# mc_psu_v2.net
KiCad netlist of a schematic drawn in EAGLE
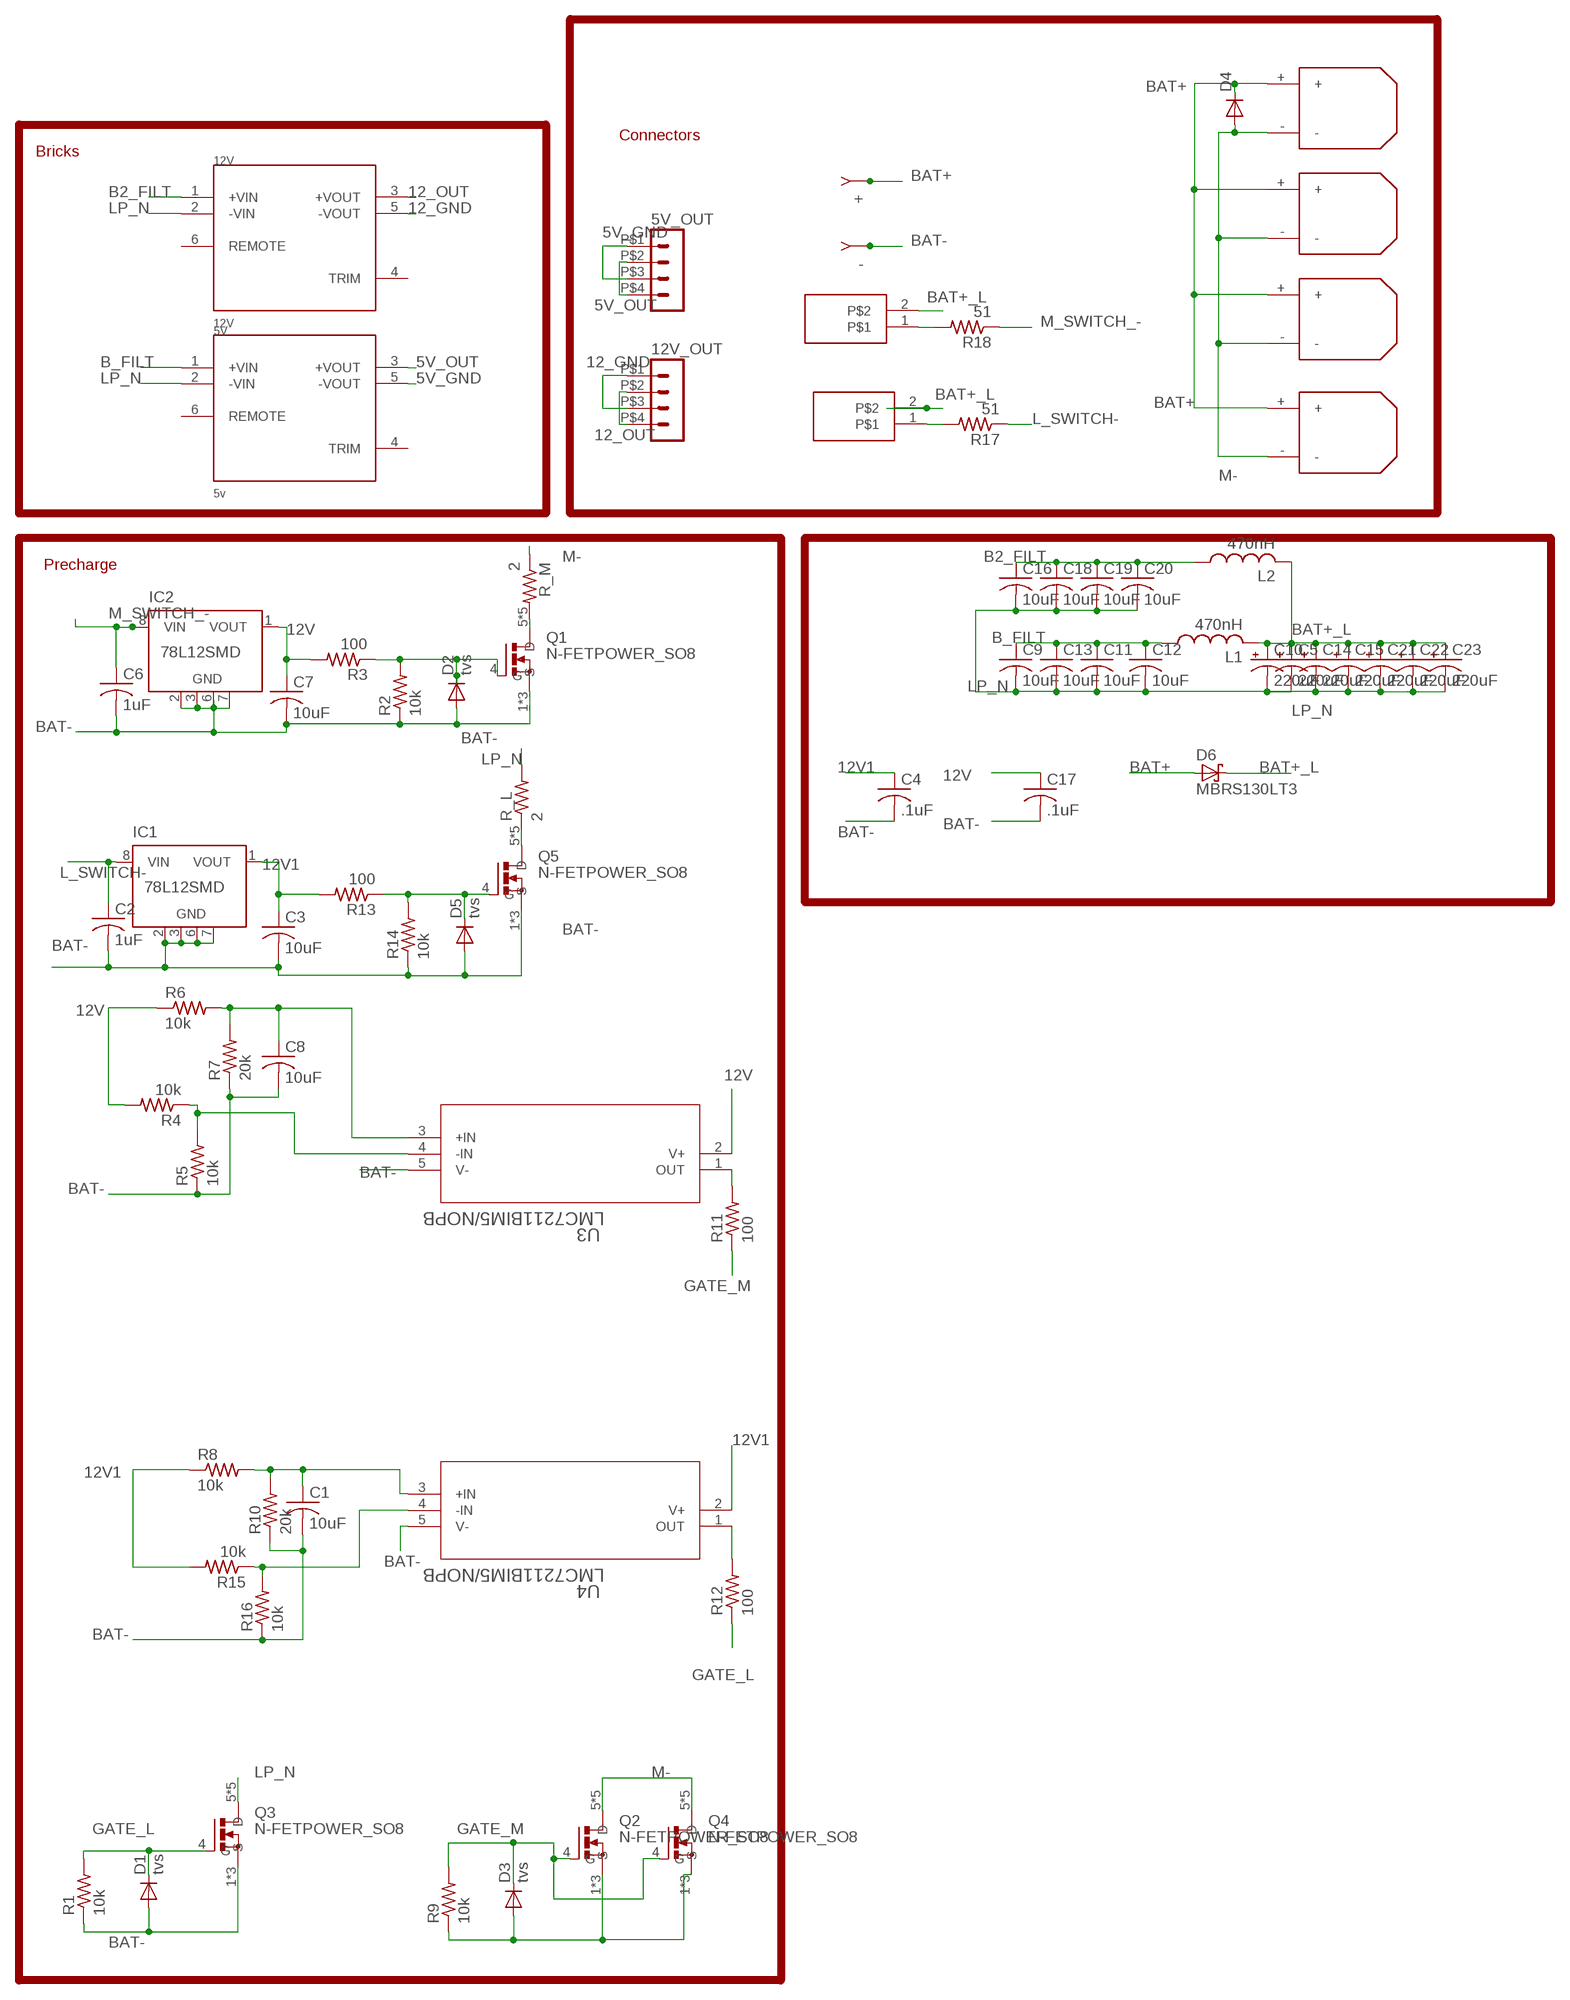
[diagram p0: schematic, sheet 1]

(export (version "E")
  (design (tool "Eeschema 10.0.6"))
  (components
    (comp (ref "+")
      (value "QFIT")
      (footprint "eagle-import:FASTON")
      (libsource (lib "eagle-import") (part "QFIT"))
    )
    (comp (ref "-")
      (value "QFIT")
      (footprint "eagle-import:FASTON")
      (libsource (lib "eagle-import") (part "QFIT"))
    )
    (comp (ref "5V")
      (value "5v")
      (footprint "eagle-import:CONV_PDQ30-Q24-S5-D")
      (fields
        (field (name "DIGI-KEY_PART_NUMBER") "102-3891-ND")
        (field (name "MF") "CUI")
        (field (name "MP") "PDQ30-Q24-S5-D")
      )
      (libsource (lib "eagle-import") (part "PDQ30-Q24-S5-D"))
    )
    (comp (ref "5V_OUT")
      (value "HEADER_POS4_43045-0401")
      (footprint "eagle-import:43045-0400")
      (libsource (lib "eagle-import") (part "HEADER_POS4_?43045-0401"))
    )
    (comp (ref "12V")
      (value "12V")
      (footprint "eagle-import:CONV_PDQ30-Q24-S5-D")
      (fields
        (field (name "DIGI-KEY_PART_NUMBER") "102-3891-ND")
        (field (name "MF") "CUI")
        (field (name "MP") "PDQ30-Q24-S5-D")
      )
      (libsource (lib "eagle-import") (part "PDQ30-Q24-S5-D"))
    )
    (comp (ref "12V_OUT")
      (value "HEADER_POS4_43045-0401")
      (footprint "eagle-import:43045-0400")
      (libsource (lib "eagle-import") (part "HEADER_POS4_?43045-0401"))
    )
    (comp (ref "C1")
      (value "10uF")
      (footprint "eagle-import:C0603K")
      (libsource (lib "eagle-import") (part "C-USC0603K"))
    )
    (comp (ref "C2")
      (value "1uF")
      (footprint "eagle-import:C0603K")
      (libsource (lib "eagle-import") (part "C-USC0603K"))
    )
    (comp (ref "C3")
      (value "10uF")
      (footprint "eagle-import:C0603K")
      (libsource (lib "eagle-import") (part "C-USC0603K"))
    )
    (comp (ref "C4")
      (value ".1uF")
      (footprint "eagle-import:C0603K")
      (libsource (lib "eagle-import") (part "C-USC0603K"))
    )
    (comp (ref "C5")
      (value "220uF")
      (footprint "eagle-import:E3,5-8")
      (libsource (lib "eagle-import") (part "CPOL-USE3.5-8"))
    )
    (comp (ref "C6")
      (value "1uF")
      (footprint "eagle-import:C0603K")
      (libsource (lib "eagle-import") (part "C-USC0603K"))
    )
    (comp (ref "C7")
      (value "10uF")
      (footprint "eagle-import:C0603K")
      (libsource (lib "eagle-import") (part "C-USC0603K"))
    )
    (comp (ref "C8")
      (value "10uF")
      (footprint "eagle-import:C0603K")
      (libsource (lib "eagle-import") (part "C-USC0603K"))
    )
    (comp (ref "C9")
      (value "10uF")
      (footprint "eagle-import:C1206K")
      (libsource (lib "eagle-import") (part "C-USC1206K"))
    )
    (comp (ref "C10")
      (value "220uF")
      (footprint "eagle-import:E3,5-8")
      (libsource (lib "eagle-import") (part "CPOL-USE3.5-8"))
    )
    (comp (ref "C11")
      (value "10uF")
      (footprint "eagle-import:C1206K")
      (libsource (lib "eagle-import") (part "C-USC1206K"))
    )
    (comp (ref "C12")
      (value "10uF")
      (footprint "eagle-import:C1206K")
      (libsource (lib "eagle-import") (part "C-USC1206K"))
    )
    (comp (ref "C13")
      (value "10uF")
      (footprint "eagle-import:C1206K")
      (libsource (lib "eagle-import") (part "C-USC1206K"))
    )
    (comp (ref "C14")
      (value "220uF")
      (footprint "eagle-import:E3,5-8")
      (libsource (lib "eagle-import") (part "CPOL-USE3.5-8"))
    )
    (comp (ref "C15")
      (value "220uF")
      (footprint "eagle-import:E3,5-8")
      (libsource (lib "eagle-import") (part "CPOL-USE3.5-8"))
    )
    (comp (ref "C16")
      (value "10uF")
      (footprint "eagle-import:C1206K")
      (libsource (lib "eagle-import") (part "C-USC1206K"))
    )
    (comp (ref "C17")
      (value ".1uF")
      (footprint "eagle-import:C0603K")
      (libsource (lib "eagle-import") (part "C-USC0603K"))
    )
    (comp (ref "C18")
      (value "10uF")
      (footprint "eagle-import:C1206K")
      (libsource (lib "eagle-import") (part "C-USC1206K"))
    )
    (comp (ref "C19")
      (value "10uF")
      (footprint "eagle-import:C1206K")
      (libsource (lib "eagle-import") (part "C-USC1206K"))
    )
    (comp (ref "C20")
      (value "10uF")
      (footprint "eagle-import:C1206K")
      (libsource (lib "eagle-import") (part "C-USC1206K"))
    )
    (comp (ref "C21")
      (value "220uF")
      (footprint "eagle-import:E3,5-8")
      (libsource (lib "eagle-import") (part "CPOL-USE3.5-8"))
    )
    (comp (ref "C22")
      (value "220uF")
      (footprint "eagle-import:E3,5-8")
      (libsource (lib "eagle-import") (part "CPOL-USE3.5-8"))
    )
    (comp (ref "C23")
      (value "220uF")
      (footprint "eagle-import:E3,5-8")
      (libsource (lib "eagle-import") (part "CPOL-USE3.5-8"))
    )
    (comp (ref "D1")
      (value "tvs")
      (footprint "eagle-import:DO214AC")
      (libsource (lib "eagle-import") (part "DIODE-DO214AC"))
    )
    (comp (ref "D2")
      (value "tvs")
      (footprint "eagle-import:DO214AC")
      (libsource (lib "eagle-import") (part "DIODE-DO214AC"))
    )
    (comp (ref "D3")
      (value "tvs")
      (footprint "eagle-import:DO214AC")
      (libsource (lib "eagle-import") (part "DIODE-DO214AC"))
    )
    (comp (ref "D4")
      (value "DIODE-SMB")
      (footprint "eagle-import:SMB")
      (libsource (lib "eagle-import") (part "DIODE-SMB"))
    )
    (comp (ref "D5")
      (value "tvs")
      (footprint "eagle-import:DO214AC")
      (libsource (lib "eagle-import") (part "DIODE-DO214AC"))
    )
    (comp (ref "D6")
      (value "MBRS130LT3")
      (footprint "eagle-import:SMB")
      (libsource (lib "eagle-import") (part "MBRS130LT3"))
    )
    (comp (ref "IC1")
      (value "78L12SMD")
      (footprint "eagle-import:SO08")
      (libsource (lib "eagle-import") (part "78LSMD12"))
    )
    (comp (ref "IC2")
      (value "78L12SMD")
      (footprint "eagle-import:SO08")
      (libsource (lib "eagle-import") (part "78LSMD12"))
    )
    (comp (ref "L1")
      (value "470nH")
      (footprint "eagle-import:L3225P")
      (libsource (lib "eagle-import") (part "L-USL3225P"))
    )
    (comp (ref "L2")
      (value "470nH")
      (footprint "eagle-import:L3225P")
      (libsource (lib "eagle-import") (part "L-USL3225P"))
    )
    (comp (ref "Q1")
      (value "N-FETPOWER_SO8")
      (footprint "eagle-import:TRANS_TPH5900CNH,L1Q")
      (libsource (lib "eagle-import") (part "N-FETPOWER_SO8"))
    )
    (comp (ref "Q2")
      (value "N-FETPOWER_SO8")
      (footprint "eagle-import:TRANS_TPH5900CNH,L1Q")
      (libsource (lib "eagle-import") (part "N-FETPOWER_SO8"))
    )
    (comp (ref "Q3")
      (value "N-FETPOWER_SO8")
      (footprint "eagle-import:TRANS_TPH5900CNH,L1Q")
      (libsource (lib "eagle-import") (part "N-FETPOWER_SO8"))
    )
    (comp (ref "Q4")
      (value "N-FETPOWER_SO8")
      (footprint "eagle-import:TRANS_TPH5900CNH,L1Q")
      (libsource (lib "eagle-import") (part "N-FETPOWER_SO8"))
    )
    (comp (ref "Q5")
      (value "N-FETPOWER_SO8")
      (footprint "eagle-import:TRANS_TPH5900CNH,L1Q")
      (libsource (lib "eagle-import") (part "N-FETPOWER_SO8"))
    )
    (comp (ref "R1")
      (value "10k")
      (footprint "eagle-import:R0402")
      (libsource (lib "eagle-import") (part "R-US_R0402"))
    )
    (comp (ref "R2")
      (value "10k")
      (footprint "eagle-import:R0402")
      (libsource (lib "eagle-import") (part "R-US_R0402"))
    )
    (comp (ref "R3")
      (value "100")
      (footprint "eagle-import:R0402")
      (libsource (lib "eagle-import") (part "R-US_R0402"))
    )
    (comp (ref "R4")
      (value "10k")
      (footprint "eagle-import:R0402")
      (libsource (lib "eagle-import") (part "R-US_R0402"))
    )
    (comp (ref "R5")
      (value "10k")
      (footprint "eagle-import:R0402")
      (libsource (lib "eagle-import") (part "R-US_R0402"))
    )
    (comp (ref "R6")
      (value "10k")
      (footprint "eagle-import:R0402")
      (libsource (lib "eagle-import") (part "R-US_R0402"))
    )
    (comp (ref "R7")
      (value "20k")
      (footprint "eagle-import:R0402")
      (libsource (lib "eagle-import") (part "R-US_R0402"))
    )
    (comp (ref "R8")
      (value "10k")
      (footprint "eagle-import:R0402")
      (libsource (lib "eagle-import") (part "R-US_R0402"))
    )
    (comp (ref "R9")
      (value "10k")
      (footprint "eagle-import:R0402")
      (libsource (lib "eagle-import") (part "R-US_R0402"))
    )
    (comp (ref "R10")
      (value "20k")
      (footprint "eagle-import:R0402")
      (libsource (lib "eagle-import") (part "R-US_R0402"))
    )
    (comp (ref "R11")
      (value "100")
      (footprint "eagle-import:R0402")
      (libsource (lib "eagle-import") (part "R-US_R0402"))
    )
    (comp (ref "R12")
      (value "100")
      (footprint "eagle-import:R0402")
      (libsource (lib "eagle-import") (part "R-US_R0402"))
    )
    (comp (ref "R13")
      (value "100")
      (footprint "eagle-import:R0402")
      (libsource (lib "eagle-import") (part "R-US_R0402"))
    )
    (comp (ref "R14")
      (value "10k")
      (footprint "eagle-import:R0402")
      (libsource (lib "eagle-import") (part "R-US_R0402"))
    )
    (comp (ref "R15")
      (value "10k")
      (footprint "eagle-import:R0402")
      (libsource (lib "eagle-import") (part "R-US_R0402"))
    )
    (comp (ref "R16")
      (value "10k")
      (footprint "eagle-import:R0402")
      (libsource (lib "eagle-import") (part "R-US_R0402"))
    )
    (comp (ref "R17")
      (value "51")
      (footprint "eagle-import:R0603")
      (libsource (lib "eagle-import") (part "R-US_R0603"))
    )
    (comp (ref "R18")
      (value "51")
      (footprint "eagle-import:R0603")
      (libsource (lib "eagle-import") (part "R-US_R0603"))
    )
    (comp (ref "R_L")
      (value "2")
      (footprint "eagle-import:D2PAK")
      (libsource (lib "eagle-import") (part "RESISTOR"))
    )
    (comp (ref "R_M")
      (value "2")
      (footprint "eagle-import:D2PAK")
      (libsource (lib "eagle-import") (part "RESISTOR"))
    )
    (comp (ref "U$3")
      (value "XT30FEMALW")
      (footprint "eagle-import:XT30_H_F")
      (libsource (lib "eagle-import") (part "XT30FEMALW"))
    )
    (comp (ref "U$8")
      (value "XT30FEMALW")
      (footprint "eagle-import:XT30_H_F")
      (libsource (lib "eagle-import") (part "XT30FEMALW"))
    )
    (comp (ref "U$9")
      (value "XT30FEMALW")
      (footprint "eagle-import:XT30_H_F")
      (libsource (lib "eagle-import") (part "XT30FEMALW"))
    )
    (comp (ref "U$10")
      (value "XT30FEMALW")
      (footprint "eagle-import:XT30_H_F")
      (libsource (lib "eagle-import") (part "XT30FEMALW"))
    )
    (comp (ref "U$13")
      (value "2-PINM80_H")
      (footprint "eagle-import:M80-840242")
      (libsource (lib "eagle-import") (part "2-PINM80_H"))
    )
    (comp (ref "U$14")
      (value "2-PINM80_H")
      (footprint "eagle-import:M80-840242")
      (libsource (lib "eagle-import") (part "2-PINM80_H"))
    )
    (comp (ref "U3")
      (value "LMC7211BIM5/NOPB")
      (footprint "eagle-import:MF05A")
      (fields (field (name "MANUFACTURER_PART_NUMBER") "LMC7211BIM5NOPB"))
      (libsource (lib "eagle-import") (part "LMC7211BIM5/NOPB"))
    )
    (comp (ref "U4")
      (value "LMC7211BIM5/NOPB")
      (footprint "eagle-import:MF05A")
      (fields (field (name "MANUFACTURER_PART_NUMBER") "LMC7211BIM5NOPB"))
      (libsource (lib "eagle-import") (part "LMC7211BIM5/NOPB"))
    )
  )
  (nets
    (net (code "1") (name "/5V_GND") (class "Default")
      (node (ref "5V") (pin "5") (pinfunction "-VOUT_5") (pintype "output"))
      (node (ref "5V_OUT") (pin "P$1") (pinfunction "1_P$1") (pintype "passive"))
      (node (ref "5V_OUT") (pin "P$3") (pinfunction "3_P$3") (pintype "passive"))
    )
    (net (code "2") (name "/5V_OUT") (class "Default")
      (node (ref "5V") (pin "3") (pinfunction "+VOUT_3") (pintype "output"))
      (node (ref "5V_OUT") (pin "P$2") (pinfunction "2_P$2") (pintype "passive"))
      (node (ref "5V_OUT") (pin "P$4") (pinfunction "4_P$4") (pintype "passive"))
    )
    (net (code "3") (name "/12V") (class "Default")
      (node (ref "C17") (pin "1") (pinfunction "1_1") (pintype "passive"))
      (node (ref "C7") (pin "1") (pinfunction "1_1") (pintype "passive"))
      (node (ref "IC2") (pin "1") (pinfunction "VOUT_1") (pintype "output"))
      (node (ref "R3") (pin "2") (pinfunction "2_2") (pintype "passive"))
      (node (ref "R4") (pin "2") (pinfunction "2_2") (pintype "passive"))
      (node (ref "R6") (pin "1") (pinfunction "1_1") (pintype "passive"))
      (node (ref "U3") (pin "2") (pinfunction "V+_2") (pintype "passive"))
    )
    (net (code "4") (name "/12V1") (class "Default")
      (node (ref "C3") (pin "1") (pinfunction "1_1") (pintype "passive"))
      (node (ref "C4") (pin "1") (pinfunction "1_1") (pintype "passive"))
      (node (ref "IC1") (pin "1") (pinfunction "VOUT_1") (pintype "output"))
      (node (ref "R13") (pin "2") (pinfunction "2_2") (pintype "passive"))
      (node (ref "R15") (pin "2") (pinfunction "2_2") (pintype "passive"))
      (node (ref "R8") (pin "1") (pinfunction "1_1") (pintype "passive"))
      (node (ref "U4") (pin "2") (pinfunction "V+_2") (pintype "passive"))
    )
    (net (code "5") (name "/12_GND") (class "Default")
      (node (ref "12V") (pin "5") (pinfunction "-VOUT_5") (pintype "output"))
      (node (ref "12V_OUT") (pin "P$1") (pinfunction "1_P$1") (pintype "passive"))
      (node (ref "12V_OUT") (pin "P$3") (pinfunction "3_P$3") (pintype "passive"))
    )
    (net (code "6") (name "/12_OUT") (class "Default")
      (node (ref "12V") (pin "3") (pinfunction "+VOUT_3") (pintype "output"))
      (node (ref "12V_OUT") (pin "P$2") (pinfunction "2_P$2") (pintype "passive"))
      (node (ref "12V_OUT") (pin "P$4") (pinfunction "4_P$4") (pintype "passive"))
    )
    (net (code "7") (name "/B2_FILT") (class "Default")
      (node (ref "12V") (pin "1") (pinfunction "+VIN_1") (pintype "input"))
      (node (ref "C16") (pin "1") (pinfunction "1_1") (pintype "passive"))
      (node (ref "C18") (pin "1") (pinfunction "1_1") (pintype "passive"))
      (node (ref "C19") (pin "1") (pinfunction "1_1") (pintype "passive"))
      (node (ref "C20") (pin "1") (pinfunction "1_1") (pintype "passive"))
      (node (ref "L2") (pin "1") (pinfunction "1_1") (pintype "passive"))
    )
    (net (code "8") (name "/BAT+") (class "Default")
      (node (ref "+") (pin "1") (pinfunction "1_1") (pintype "passive"))
      (node (ref "+") (pin "2") (pinfunction "2_2") (pintype "passive"))
      (node (ref "D4") (pin "C") (pinfunction "C_C") (pintype "passive"))
      (node (ref "D6") (pin "A") (pinfunction "A_A") (pintype "passive"))
      (node (ref "U$10") (pin "+") (pinfunction "+_+") (pintype "bidirectional"))
      (node (ref "U$3") (pin "+") (pinfunction "+_+") (pintype "bidirectional"))
      (node (ref "U$8") (pin "+") (pinfunction "+_+") (pintype "bidirectional"))
      (node (ref "U$9") (pin "+") (pinfunction "+_+") (pintype "bidirectional"))
    )
    (net (code "9") (name "/BAT+_L") (class "Default")
      (node (ref "C10") (pin "+") (pinfunction "+_+") (pintype "passive"))
      (node (ref "C14") (pin "+") (pinfunction "+_+") (pintype "passive"))
      (node (ref "C15") (pin "+") (pinfunction "+_+") (pintype "passive"))
      (node (ref "C21") (pin "+") (pinfunction "+_+") (pintype "passive"))
      (node (ref "C22") (pin "+") (pinfunction "+_+") (pintype "passive"))
      (node (ref "C23") (pin "+") (pinfunction "+_+") (pintype "passive"))
      (node (ref "C5") (pin "+") (pinfunction "+_+") (pintype "passive"))
      (node (ref "D6") (pin "C") (pinfunction "C_C") (pintype "passive"))
      (node (ref "L1") (pin "2") (pinfunction "2_2") (pintype "passive"))
      (node (ref "L2") (pin "2") (pinfunction "2_2") (pintype "passive"))
      (node (ref "U$13") (pin "2") (pinfunction "P$2_2") (pintype "bidirectional"))
      (node (ref "U$14") (pin "2") (pinfunction "P$2_2") (pintype "bidirectional"))
    )
    (net (code "10") (name "/BAT-") (class "Default")
      (node (ref "-") (pin "1") (pinfunction "1_1") (pintype "passive"))
      (node (ref "-") (pin "2") (pinfunction "2_2") (pintype "passive"))
      (node (ref "C1") (pin "2") (pinfunction "2_2") (pintype "passive"))
      (node (ref "C17") (pin "2") (pinfunction "2_2") (pintype "passive"))
      (node (ref "C2") (pin "2") (pinfunction "2_2") (pintype "passive"))
      (node (ref "C3") (pin "2") (pinfunction "2_2") (pintype "passive"))
      (node (ref "C4") (pin "2") (pinfunction "2_2") (pintype "passive"))
      (node (ref "C6") (pin "2") (pinfunction "2_2") (pintype "passive"))
      (node (ref "C7") (pin "2") (pinfunction "2_2") (pintype "passive"))
      (node (ref "C8") (pin "2") (pinfunction "2_2") (pintype "passive"))
      (node (ref "D1") (pin "A") (pinfunction "A_A") (pintype "passive"))
      (node (ref "D2") (pin "A") (pinfunction "A_A") (pintype "passive"))
      (node (ref "D3") (pin "A") (pinfunction "A_A") (pintype "passive"))
      (node (ref "D5") (pin "A") (pinfunction "A_A") (pintype "passive"))
      (node (ref "IC1") (pin "2") (pinfunction "GND_2") (pintype "power_in"))
      (node (ref "IC1") (pin "3") (pinfunction "GND_3") (pintype "power_in"))
      (node (ref "IC1") (pin "6") (pinfunction "GND_6") (pintype "power_in"))
      (node (ref "IC1") (pin "7") (pinfunction "GND_7") (pintype "power_in"))
      (node (ref "IC2") (pin "2") (pinfunction "GND_2") (pintype "power_in"))
      (node (ref "IC2") (pin "3") (pinfunction "GND_3") (pintype "power_in"))
      (node (ref "IC2") (pin "6") (pinfunction "GND_6") (pintype "power_in"))
      (node (ref "IC2") (pin "7") (pinfunction "GND_7") (pintype "power_in"))
      (node (ref "Q1") (pin "1") (pinfunction "S_1") (pintype "bidirectional"))
      (node (ref "Q1") (pin "2") (pinfunction "S_2") (pintype "bidirectional"))
      (node (ref "Q1") (pin "3") (pinfunction "S_3") (pintype "bidirectional"))
      (node (ref "Q2") (pin "1") (pinfunction "S_1") (pintype "bidirectional"))
      (node (ref "Q2") (pin "2") (pinfunction "S_2") (pintype "bidirectional"))
      (node (ref "Q2") (pin "3") (pinfunction "S_3") (pintype "bidirectional"))
      (node (ref "Q3") (pin "1") (pinfunction "S_1") (pintype "bidirectional"))
      (node (ref "Q3") (pin "2") (pinfunction "S_2") (pintype "bidirectional"))
      (node (ref "Q3") (pin "3") (pinfunction "S_3") (pintype "bidirectional"))
      (node (ref "Q4") (pin "1") (pinfunction "S_1") (pintype "bidirectional"))
      (node (ref "Q4") (pin "2") (pinfunction "S_2") (pintype "bidirectional"))
      (node (ref "Q4") (pin "3") (pinfunction "S_3") (pintype "bidirectional"))
      (node (ref "Q5") (pin "1") (pinfunction "S_1") (pintype "bidirectional"))
      (node (ref "Q5") (pin "2") (pinfunction "S_2") (pintype "bidirectional"))
      (node (ref "Q5") (pin "3") (pinfunction "S_3") (pintype "bidirectional"))
      (node (ref "R1") (pin "1") (pinfunction "1_1") (pintype "passive"))
      (node (ref "R10") (pin "1") (pinfunction "1_1") (pintype "passive"))
      (node (ref "R14") (pin "1") (pinfunction "1_1") (pintype "passive"))
      (node (ref "R16") (pin "1") (pinfunction "1_1") (pintype "passive"))
      (node (ref "R2") (pin "1") (pinfunction "1_1") (pintype "passive"))
      (node (ref "R5") (pin "1") (pinfunction "1_1") (pintype "passive"))
      (node (ref "R7") (pin "1") (pinfunction "1_1") (pintype "passive"))
      (node (ref "R9") (pin "1") (pinfunction "1_1") (pintype "passive"))
      (node (ref "U3") (pin "5") (pinfunction "V-_5") (pintype "passive"))
      (node (ref "U4") (pin "5") (pinfunction "V-_5") (pintype "passive"))
    )
    (net (code "11") (name "/B_FILT") (class "Default")
      (node (ref "5V") (pin "1") (pinfunction "+VIN_1") (pintype "input"))
      (node (ref "C11") (pin "1") (pinfunction "1_1") (pintype "passive"))
      (node (ref "C12") (pin "1") (pinfunction "1_1") (pintype "passive"))
      (node (ref "C13") (pin "1") (pinfunction "1_1") (pintype "passive"))
      (node (ref "C9") (pin "1") (pinfunction "1_1") (pintype "passive"))
      (node (ref "L1") (pin "1") (pinfunction "1_1") (pintype "passive"))
    )
    (net (code "12") (name "/GATE_L") (class "Default")
      (node (ref "D1") (pin "C") (pinfunction "C_C") (pintype "passive"))
      (node (ref "Q3") (pin "4") (pinfunction "G_4") (pintype "bidirectional"))
      (node (ref "R1") (pin "2") (pinfunction "2_2") (pintype "passive"))
      (node (ref "R12") (pin "1") (pinfunction "1_1") (pintype "passive"))
    )
    (net (code "13") (name "/GATE_M") (class "Default")
      (node (ref "D3") (pin "C") (pinfunction "C_C") (pintype "passive"))
      (node (ref "Q2") (pin "4") (pinfunction "G_4") (pintype "bidirectional"))
      (node (ref "Q4") (pin "4") (pinfunction "G_4") (pintype "bidirectional"))
      (node (ref "R11") (pin "1") (pinfunction "1_1") (pintype "passive"))
      (node (ref "R9") (pin "2") (pinfunction "2_2") (pintype "passive"))
    )
    (net (code "14") (name "/LP_N") (class "Default")
      (node (ref "12V") (pin "2") (pinfunction "-VIN_2") (pintype "input"))
      (node (ref "5V") (pin "2") (pinfunction "-VIN_2") (pintype "input"))
      (node (ref "C10") (pin "-") (pinfunction "-_-") (pintype "passive"))
      (node (ref "C11") (pin "2") (pinfunction "2_2") (pintype "passive"))
      (node (ref "C12") (pin "2") (pinfunction "2_2") (pintype "passive"))
      (node (ref "C13") (pin "2") (pinfunction "2_2") (pintype "passive"))
      (node (ref "C14") (pin "-") (pinfunction "-_-") (pintype "passive"))
      (node (ref "C15") (pin "-") (pinfunction "-_-") (pintype "passive"))
      (node (ref "C16") (pin "2") (pinfunction "2_2") (pintype "passive"))
      (node (ref "C18") (pin "2") (pinfunction "2_2") (pintype "passive"))
      (node (ref "C19") (pin "2") (pinfunction "2_2") (pintype "passive"))
      (node (ref "C20") (pin "2") (pinfunction "2_2") (pintype "passive"))
      (node (ref "C21") (pin "-") (pinfunction "-_-") (pintype "passive"))
      (node (ref "C22") (pin "-") (pinfunction "-_-") (pintype "passive"))
      (node (ref "C23") (pin "-") (pinfunction "-_-") (pintype "passive"))
      (node (ref "C5") (pin "-") (pinfunction "-_-") (pintype "passive"))
      (node (ref "C9") (pin "2") (pinfunction "2_2") (pintype "passive"))
      (node (ref "Q3") (pin "5") (pinfunction "D_5") (pintype "bidirectional"))
      (node (ref "Q3") (pin "6") (pinfunction "D_6") (pintype "bidirectional"))
      (node (ref "Q3") (pin "7") (pinfunction "D_7") (pintype "bidirectional"))
      (node (ref "Q3") (pin "8") (pinfunction "D_8") (pintype "bidirectional"))
      (node (ref "Q3") (pin "EP") (pinfunction "D_EP") (pintype "bidirectional"))
      (node (ref "R_L") (pin "3") (pinfunction "2_3") (pintype "passive"))
    )
    (net (code "15") (name "/L_SWITCH-") (class "Default")
      (node (ref "C2") (pin "1") (pinfunction "1_1") (pintype "passive"))
      (node (ref "IC1") (pin "8") (pinfunction "VIN_8") (pintype "passive"))
      (node (ref "R17") (pin "1") (pinfunction "1_1") (pintype "passive"))
    )
    (net (code "16") (name "/M-") (class "Default")
      (node (ref "D4") (pin "A") (pinfunction "A_A") (pintype "passive"))
      (node (ref "Q2") (pin "5") (pinfunction "D_5") (pintype "bidirectional"))
      (node (ref "Q2") (pin "6") (pinfunction "D_6") (pintype "bidirectional"))
      (node (ref "Q2") (pin "7") (pinfunction "D_7") (pintype "bidirectional"))
      (node (ref "Q2") (pin "8") (pinfunction "D_8") (pintype "bidirectional"))
      (node (ref "Q2") (pin "EP") (pinfunction "D_EP") (pintype "bidirectional"))
      (node (ref "Q4") (pin "5") (pinfunction "D_5") (pintype "bidirectional"))
      (node (ref "Q4") (pin "6") (pinfunction "D_6") (pintype "bidirectional"))
      (node (ref "Q4") (pin "7") (pinfunction "D_7") (pintype "bidirectional"))
      (node (ref "Q4") (pin "8") (pinfunction "D_8") (pintype "bidirectional"))
      (node (ref "Q4") (pin "EP") (pinfunction "D_EP") (pintype "bidirectional"))
      (node (ref "R_M") (pin "1") (pinfunction "1_1") (pintype "passive"))
      (node (ref "U$10") (pin "-") (pinfunction "-_-") (pintype "bidirectional"))
      (node (ref "U$3") (pin "-") (pinfunction "-_-") (pintype "bidirectional"))
      (node (ref "U$8") (pin "-") (pinfunction "-_-") (pintype "bidirectional"))
      (node (ref "U$9") (pin "-") (pinfunction "-_-") (pintype "bidirectional"))
    )
    (net (code "17") (name "/M_SWITCH_-") (class "Default")
      (node (ref "C6") (pin "1") (pinfunction "1_1") (pintype "passive"))
      (node (ref "IC2") (pin "8") (pinfunction "VIN_8") (pintype "passive"))
      (node (ref "R18") (pin "1") (pinfunction "1_1") (pintype "passive"))
    )
    (net (code "18") (name "Net-(Q1-G)") (class "Default")
      (node (ref "D2") (pin "C") (pinfunction "C_C") (pintype "passive"))
      (node (ref "Q1") (pin "4") (pinfunction "G_4") (pintype "bidirectional"))
      (node (ref "R2") (pin "2") (pinfunction "2_2") (pintype "passive"))
      (node (ref "R3") (pin "1") (pinfunction "1_1") (pintype "passive"))
    )
    (net (code "19") (name "Net-(Q5-D-Pad5)") (class "Default")
      (node (ref "Q5") (pin "5") (pinfunction "D_5") (pintype "bidirectional"))
      (node (ref "Q5") (pin "6") (pinfunction "D_6") (pintype "bidirectional"))
      (node (ref "Q5") (pin "7") (pinfunction "D_7") (pintype "bidirectional"))
      (node (ref "Q5") (pin "8") (pinfunction "D_8") (pintype "bidirectional"))
      (node (ref "Q5") (pin "EP") (pinfunction "D_EP") (pintype "bidirectional"))
      (node (ref "R_L") (pin "1") (pinfunction "1_1") (pintype "passive"))
    )
    (net (code "20") (name "Net-(Q5-G)") (class "Default")
      (node (ref "D5") (pin "C") (pinfunction "C_C") (pintype "passive"))
      (node (ref "Q5") (pin "4") (pinfunction "G_4") (pintype "bidirectional"))
      (node (ref "R13") (pin "1") (pinfunction "1_1") (pintype "passive"))
      (node (ref "R14") (pin "2") (pinfunction "2_2") (pintype "passive"))
    )
    (net (code "21") (name "Net-(R_M-2)") (class "Default")
      (node (ref "Q1") (pin "5") (pinfunction "D_5") (pintype "bidirectional"))
      (node (ref "Q1") (pin "6") (pinfunction "D_6") (pintype "bidirectional"))
      (node (ref "Q1") (pin "7") (pinfunction "D_7") (pintype "bidirectional"))
      (node (ref "Q1") (pin "8") (pinfunction "D_8") (pintype "bidirectional"))
      (node (ref "Q1") (pin "EP") (pinfunction "D_EP") (pintype "bidirectional"))
      (node (ref "R_M") (pin "3") (pinfunction "2_3") (pintype "passive"))
    )
    (net (code "22") (name "Net-(U$13-P$1)") (class "Default")
      (node (ref "R18") (pin "2") (pinfunction "2_2") (pintype "passive"))
      (node (ref "U$13") (pin "1") (pinfunction "P$1_1") (pintype "bidirectional"))
    )
    (net (code "23") (name "Net-(U$14-P$1)") (class "Default")
      (node (ref "R17") (pin "2") (pinfunction "2_2") (pintype "passive"))
      (node (ref "U$14") (pin "1") (pinfunction "P$1_1") (pintype "bidirectional"))
    )
    (net (code "24") (name "Net-(U3-+IN)") (class "Default")
      (node (ref "C8") (pin "1") (pinfunction "1_1") (pintype "passive"))
      (node (ref "R6") (pin "2") (pinfunction "2_2") (pintype "passive"))
      (node (ref "R7") (pin "2") (pinfunction "2_2") (pintype "passive"))
      (node (ref "U3") (pin "3") (pinfunction "+IN_3") (pintype "input"))
    )
    (net (code "25") (name "Net-(U3--IN)") (class "Default")
      (node (ref "R4") (pin "1") (pinfunction "1_1") (pintype "passive"))
      (node (ref "R5") (pin "2") (pinfunction "2_2") (pintype "passive"))
      (node (ref "U3") (pin "4") (pinfunction "-IN_4") (pintype "input"))
    )
    (net (code "26") (name "Net-(U3-OUT)") (class "Default")
      (node (ref "R11") (pin "2") (pinfunction "2_2") (pintype "passive"))
      (node (ref "U3") (pin "1") (pinfunction "OUT_1") (pintype "output"))
    )
    (net (code "27") (name "Net-(U4-+IN)") (class "Default")
      (node (ref "C1") (pin "1") (pinfunction "1_1") (pintype "passive"))
      (node (ref "R10") (pin "2") (pinfunction "2_2") (pintype "passive"))
      (node (ref "R8") (pin "2") (pinfunction "2_2") (pintype "passive"))
      (node (ref "U4") (pin "3") (pinfunction "+IN_3") (pintype "input"))
    )
    (net (code "28") (name "Net-(U4--IN)") (class "Default")
      (node (ref "R15") (pin "1") (pinfunction "1_1") (pintype "passive"))
      (node (ref "R16") (pin "2") (pinfunction "2_2") (pintype "passive"))
      (node (ref "U4") (pin "4") (pinfunction "-IN_4") (pintype "input"))
    )
    (net (code "29") (name "Net-(U4-OUT)") (class "Default")
      (node (ref "R12") (pin "2") (pinfunction "2_2") (pintype "passive"))
      (node (ref "U4") (pin "1") (pinfunction "OUT_1") (pintype "output"))
    )
    (net (code "30") (name "unconnected-(5V-REMOTE-Pad6)") (class "Default")
      (node (ref "5V") (pin "6") (pinfunction "REMOTE_6") (pintype "input"))
    )
    (net (code "31") (name "unconnected-(5V-TRIM-Pad4)") (class "Default")
      (node (ref "5V") (pin "4") (pinfunction "TRIM_4") (pintype "passive"))
    )
    (net (code "32") (name "unconnected-(12V-REMOTE-Pad6)") (class "Default")
      (node (ref "12V") (pin "6") (pinfunction "REMOTE_6") (pintype "input"))
    )
    (net (code "33") (name "unconnected-(12V-TRIM-Pad4)") (class "Default")
      (node (ref "12V") (pin "4") (pinfunction "TRIM_4") (pintype "passive"))
    )
  )
)
